# FOTA.net
KiCad netlist of a schematic drawn in Altium Designer
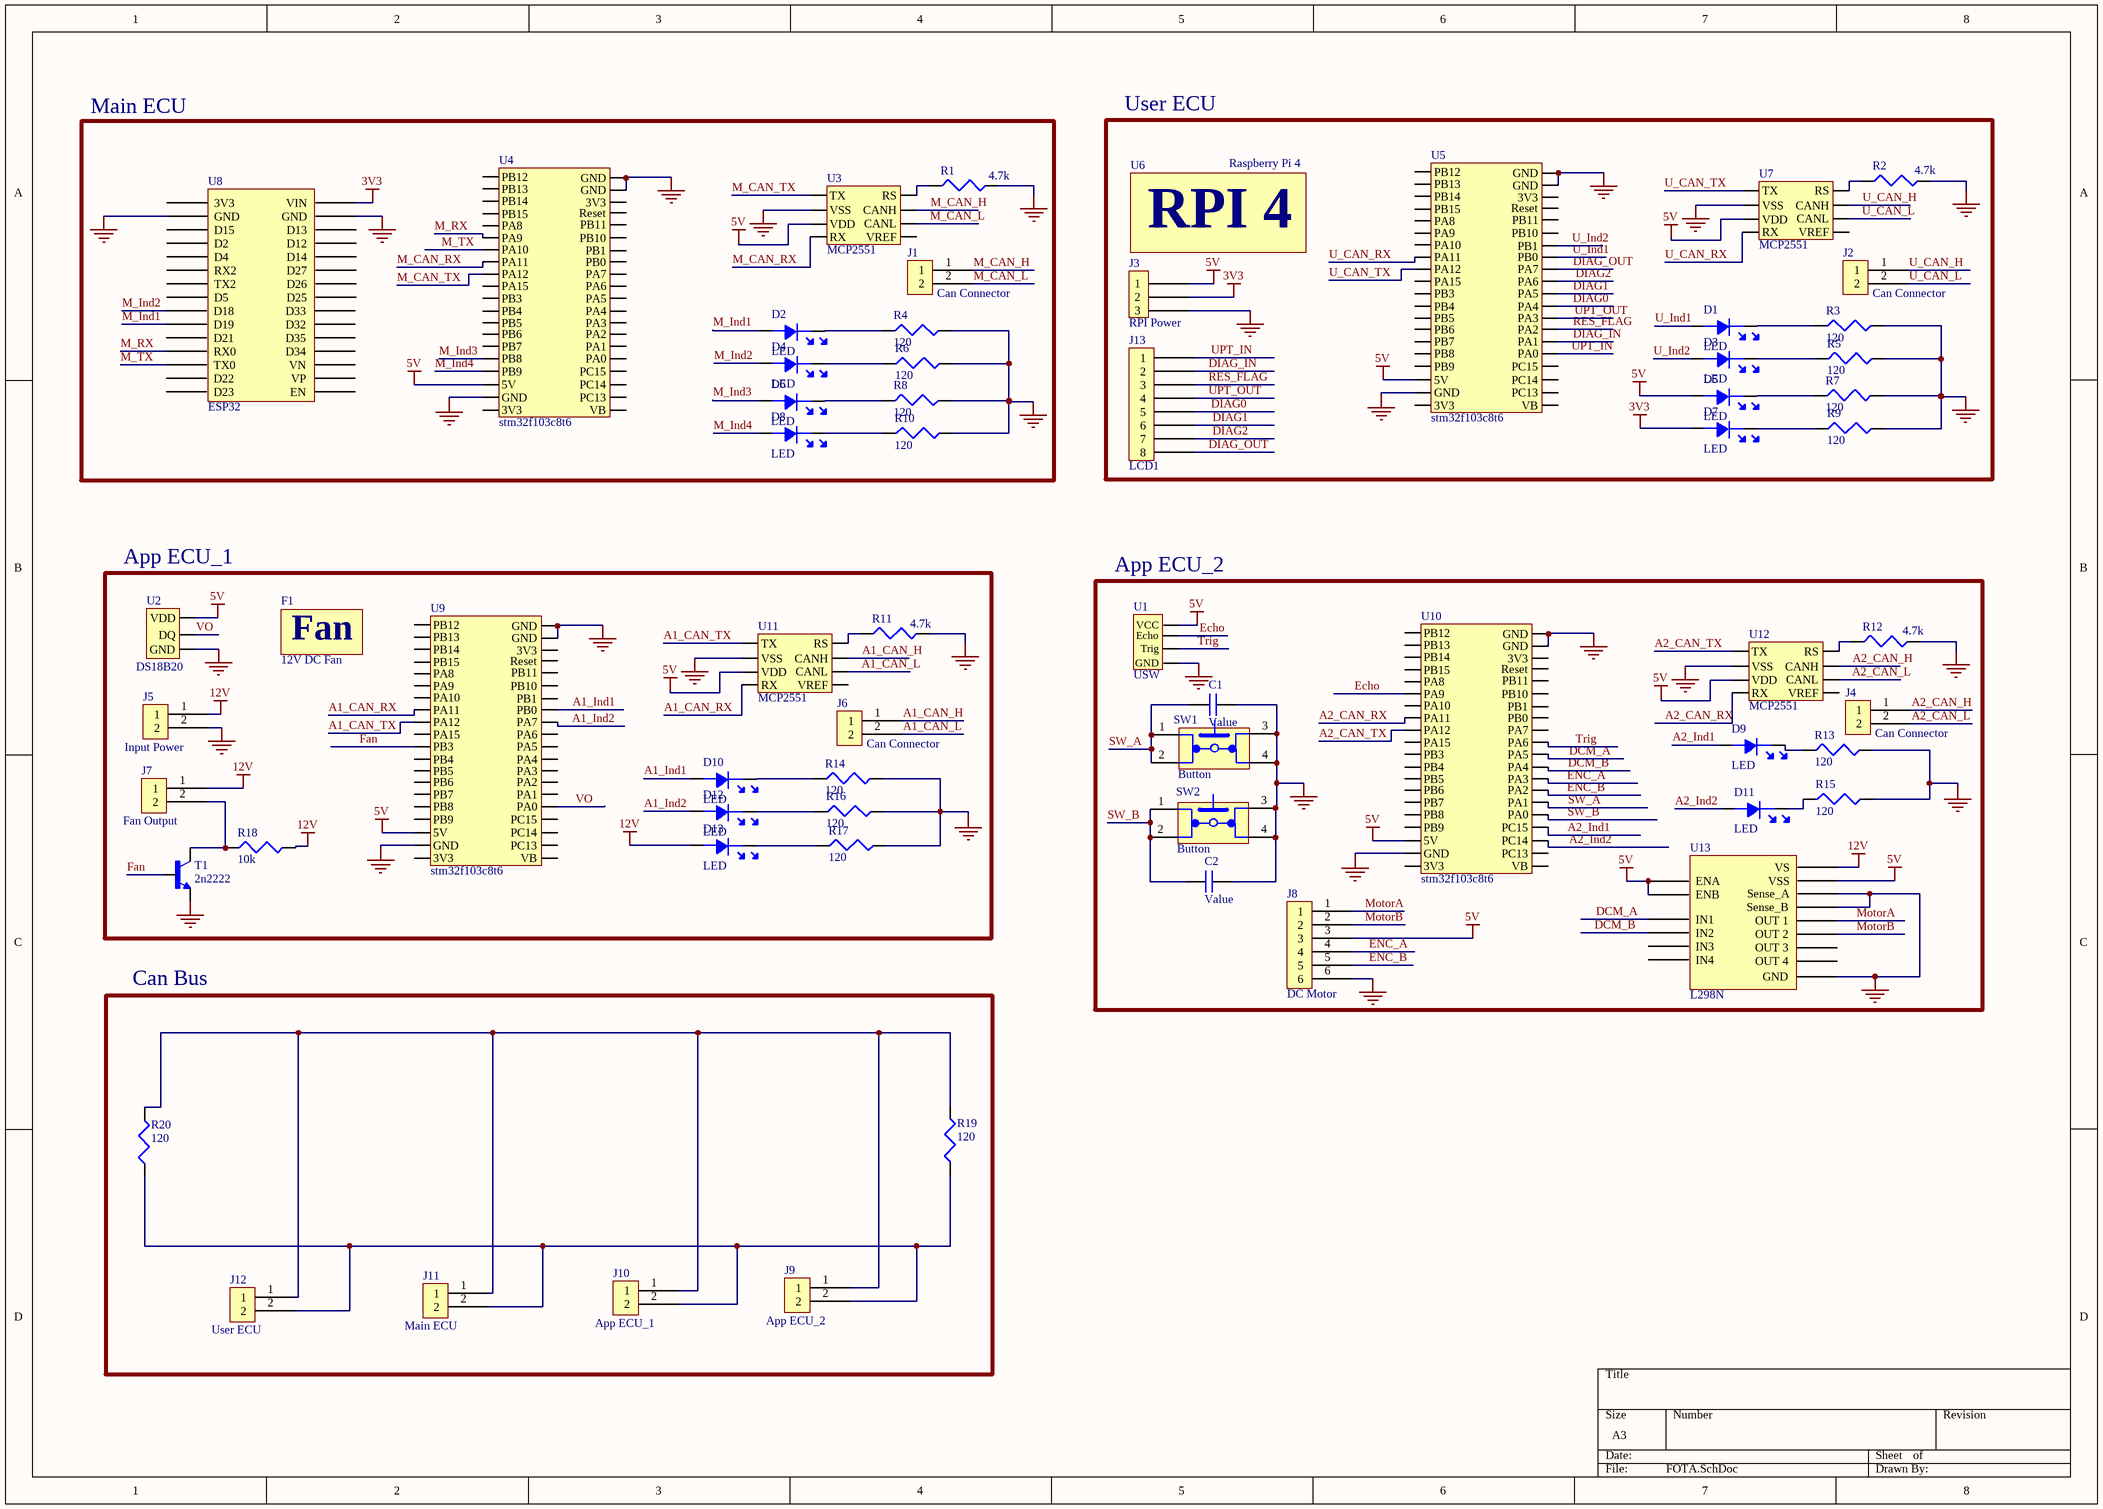
[diagram p0: FOTA.SchDoc]

(export (version "E")
  (design (tool "Eeschema 10.0.6"))
  (components
    (comp (ref "C1")
      (value "Value")
      (footprint "CAP non")
      (description "Generial Non polarized capacitor for through hole or SMD capacitors")
      (libsource (lib "FOTA") (part "Non polarized capacitor"))
    )
    (comp (ref "C2")
      (value "Value")
      (footprint "CAP non")
      (description "Generial Non polarized capacitor for through hole or SMD capacitors")
      (libsource (lib "FOTA") (part "Non polarized capacitor"))
    )
    (comp (ref "D1")
      (value "LED")
      (footprint "LED")
      (description "Led, Red, T-1 (3Mm), 630 Nm, 1.8 V, 30 Ma, 20 Mcd Rohs Compliant: Yes")
      (libsource (lib "FOTA") (part "LED"))
    )
    (comp (ref "D2")
      (value "LED")
      (footprint "LED")
      (description "Led, Red, T-1 (3Mm), 630 Nm, 1.8 V, 30 Ma, 20 Mcd Rohs Compliant: Yes")
      (libsource (lib "FOTA") (part "LED"))
    )
    (comp (ref "D3")
      (value "LED")
      (footprint "LED")
      (description "Led, Red, T-1 (3Mm), 630 Nm, 1.8 V, 30 Ma, 20 Mcd Rohs Compliant: Yes")
      (libsource (lib "FOTA") (part "LED"))
    )
    (comp (ref "D4")
      (value "LED")
      (footprint "LED")
      (description "Led, Red, T-1 (3Mm), 630 Nm, 1.8 V, 30 Ma, 20 Mcd Rohs Compliant: Yes")
      (libsource (lib "FOTA") (part "LED"))
    )
    (comp (ref "D5")
      (value "LED")
      (footprint "LED")
      (description "Led, Red, T-1 (3Mm), 630 Nm, 1.8 V, 30 Ma, 20 Mcd Rohs Compliant: Yes")
      (libsource (lib "FOTA") (part "LED"))
    )
    (comp (ref "D6")
      (value "LED")
      (footprint "LED")
      (description "Led, Red, T-1 (3Mm), 630 Nm, 1.8 V, 30 Ma, 20 Mcd Rohs Compliant: Yes")
      (libsource (lib "FOTA") (part "LED"))
    )
    (comp (ref "D7")
      (value "LED")
      (footprint "LED")
      (description "Led, Red, T-1 (3Mm), 630 Nm, 1.8 V, 30 Ma, 20 Mcd Rohs Compliant: Yes")
      (libsource (lib "FOTA") (part "LED"))
    )
    (comp (ref "D8")
      (value "LED")
      (footprint "LED")
      (description "Led, Red, T-1 (3Mm), 630 Nm, 1.8 V, 30 Ma, 20 Mcd Rohs Compliant: Yes")
      (libsource (lib "FOTA") (part "LED"))
    )
    (comp (ref "D9")
      (value "LED")
      (footprint "LED")
      (description "Led, Red, T-1 (3Mm), 630 Nm, 1.8 V, 30 Ma, 20 Mcd Rohs Compliant: Yes")
      (libsource (lib "FOTA") (part "LED"))
    )
    (comp (ref "D10")
      (value "LED")
      (footprint "LED")
      (description "Led, Red, T-1 (3Mm), 630 Nm, 1.8 V, 30 Ma, 20 Mcd Rohs Compliant: Yes")
      (libsource (lib "FOTA") (part "LED"))
    )
    (comp (ref "D11")
      (value "LED")
      (footprint "LED")
      (description "Led, Red, T-1 (3Mm), 630 Nm, 1.8 V, 30 Ma, 20 Mcd Rohs Compliant: Yes")
      (libsource (lib "FOTA") (part "LED"))
    )
    (comp (ref "D12")
      (value "LED")
      (footprint "LED")
      (description "Led, Red, T-1 (3Mm), 630 Nm, 1.8 V, 30 Ma, 20 Mcd Rohs Compliant: Yes")
      (libsource (lib "FOTA") (part "LED"))
    )
    (comp (ref "D13")
      (value "LED")
      (footprint "LED")
      (description "Led, Red, T-1 (3Mm), 630 Nm, 1.8 V, 30 Ma, 20 Mcd Rohs Compliant: Yes")
      (libsource (lib "FOTA") (part "LED"))
    )
    (comp (ref "F1") (value "12V DC Fan") (libsource (lib "FOTA") (part "Fan")))
    (comp (ref "J1")
      (value "Can Connector")
      (footprint "Data Connnector 2 pins")
      (libsource (lib "FOTA") (part "Data Connector 2 pins"))
    )
    (comp (ref "J2")
      (value "Can Connector")
      (footprint "Data Connnector 2 pins")
      (libsource (lib "FOTA") (part "Data Connector 2 pins"))
    )
    (comp (ref "J3")
      (value "RPI Power")
      (footprint "Data Connnector 3 pins")
      (libsource (lib "FOTA") (part "Data Connector 3 pin"))
    )
    (comp (ref "J4")
      (value "Can Connector")
      (footprint "Data Connnector 2 pins")
      (libsource (lib "FOTA") (part "Data Connector 2 pins"))
    )
    (comp (ref "J5")
      (value "Input Power")
      (footprint "Data Connnector 2 pins")
      (libsource (lib "FOTA") (part "Data Connector 2 pins"))
    )
    (comp (ref "J6")
      (value "Can Connector")
      (footprint "Data Connnector 2 pins")
      (libsource (lib "FOTA") (part "Data Connector 2 pins"))
    )
    (comp (ref "J7")
      (value "Fan Output")
      (footprint "Data Connnector 2 pins")
      (libsource (lib "FOTA") (part "Data Connector 2 pins"))
    )
    (comp (ref "J8")
      (value "DC Motor")
      (footprint "Data Connnector 6 pins")
      (libsource (lib "FOTA") (part "Data Connector 6 pin"))
    )
    (comp (ref "J9")
      (value "App ECU_2")
      (footprint "Data Connnector 2 pins")
      (libsource (lib "FOTA") (part "Data Connector 2 pins"))
    )
    (comp (ref "J10")
      (value "App ECU_1")
      (footprint "Data Connnector 2 pins")
      (libsource (lib "FOTA") (part "Data Connector 2 pins"))
    )
    (comp (ref "J11")
      (value "Main ECU")
      (footprint "Data Connnector 2 pins")
      (libsource (lib "FOTA") (part "Data Connector 2 pins"))
    )
    (comp (ref "J12")
      (value "User ECU")
      (footprint "Data Connnector 2 pins")
      (libsource (lib "FOTA") (part "Data Connector 2 pins"))
    )
    (comp (ref "J13")
      (value "LCD1")
      (footprint "Data Connector 8 pins")
      (libsource (lib "FOTA") (part "Data Connector 8 pins"))
    )
    (comp (ref "R1")
      (value "4.7k")
      (footprint "4.7k")
      (description "Res Carbon Film 4.7K Ohm 5% 1/4W -500ppm/°C to 350ppm/°C Conformal AXL Thru-Hole Paper T/R")
      (fields (field (name "TOLERANCE") "5%"))
      (libsource (lib "FOTA") (part "R 4K7"))
    )
    (comp (ref "R2")
      (value "4.7k")
      (footprint "4.7k")
      (description "Res Carbon Film 4.7K Ohm 5% 1/4W -500ppm/°C to 350ppm/°C Conformal AXL Thru-Hole Paper T/R")
      (fields (field (name "TOLERANCE") "5%"))
      (libsource (lib "FOTA") (part "R 4K7"))
    )
    (comp (ref "R3")
      (value "120")
      (footprint "R120")
      (description "General Type Carbon Film Resistor 120Ohm 1/4W 5% Axial Bulk")
      (fields (field (name "TOLERANCE") "5%"))
      (libsource (lib "FOTA") (part "R120"))
    )
    (comp (ref "R4")
      (value "120")
      (footprint "R120")
      (description "General Type Carbon Film Resistor 120Ohm 1/4W 5% Axial Bulk")
      (fields (field (name "TOLERANCE") "5%"))
      (libsource (lib "FOTA") (part "R120"))
    )
    (comp (ref "R5")
      (value "120")
      (footprint "R120")
      (description "General Type Carbon Film Resistor 120Ohm 1/4W 5% Axial Bulk")
      (fields (field (name "TOLERANCE") "5%"))
      (libsource (lib "FOTA") (part "R120"))
    )
    (comp (ref "R6")
      (value "120")
      (footprint "R120")
      (description "General Type Carbon Film Resistor 120Ohm 1/4W 5% Axial Bulk")
      (fields (field (name "TOLERANCE") "5%"))
      (libsource (lib "FOTA") (part "R120"))
    )
    (comp (ref "R7")
      (value "120")
      (footprint "R120")
      (description "General Type Carbon Film Resistor 120Ohm 1/4W 5% Axial Bulk")
      (fields (field (name "TOLERANCE") "5%"))
      (libsource (lib "FOTA") (part "R120"))
    )
    (comp (ref "R8")
      (value "120")
      (footprint "R120")
      (description "General Type Carbon Film Resistor 120Ohm 1/4W 5% Axial Bulk")
      (fields (field (name "TOLERANCE") "5%"))
      (libsource (lib "FOTA") (part "R120"))
    )
    (comp (ref "R9")
      (value "120")
      (footprint "R120")
      (description "General Type Carbon Film Resistor 120Ohm 1/4W 5% Axial Bulk")
      (fields (field (name "TOLERANCE") "5%"))
      (libsource (lib "FOTA") (part "R120"))
    )
    (comp (ref "R10")
      (value "120")
      (footprint "R120")
      (description "General Type Carbon Film Resistor 120Ohm 1/4W 5% Axial Bulk")
      (fields (field (name "TOLERANCE") "5%"))
      (libsource (lib "FOTA") (part "R120"))
    )
    (comp (ref "R11")
      (value "4.7k")
      (footprint "4.7k")
      (description "Res Carbon Film 4.7K Ohm 5% 1/4W -500ppm/°C to 350ppm/°C Conformal AXL Thru-Hole Paper T/R")
      (fields (field (name "TOLERANCE") "5%"))
      (libsource (lib "FOTA") (part "R 4K7"))
    )
    (comp (ref "R12")
      (value "4.7k")
      (footprint "4.7k")
      (description "Res Carbon Film 4.7K Ohm 5% 1/4W -500ppm/°C to 350ppm/°C Conformal AXL Thru-Hole Paper T/R")
      (fields (field (name "TOLERANCE") "5%"))
      (libsource (lib "FOTA") (part "R 4K7"))
    )
    (comp (ref "R13")
      (value "120")
      (footprint "R120")
      (description "General Type Carbon Film Resistor 120Ohm 1/4W 5% Axial Bulk")
      (fields (field (name "TOLERANCE") "5%"))
      (libsource (lib "FOTA") (part "R120"))
    )
    (comp (ref "R14")
      (value "120")
      (footprint "R120")
      (description "General Type Carbon Film Resistor 120Ohm 1/4W 5% Axial Bulk")
      (fields (field (name "TOLERANCE") "5%"))
      (libsource (lib "FOTA") (part "R120"))
    )
    (comp (ref "R15")
      (value "120")
      (footprint "R120")
      (description "General Type Carbon Film Resistor 120Ohm 1/4W 5% Axial Bulk")
      (fields (field (name "TOLERANCE") "5%"))
      (libsource (lib "FOTA") (part "R120"))
    )
    (comp (ref "R16")
      (value "120")
      (footprint "R120")
      (description "General Type Carbon Film Resistor 120Ohm 1/4W 5% Axial Bulk")
      (fields (field (name "TOLERANCE") "5%"))
      (libsource (lib "FOTA") (part "R120"))
    )
    (comp (ref "R17")
      (value "120")
      (footprint "R120")
      (description "General Type Carbon Film Resistor 120Ohm 1/4W 5% Axial Bulk")
      (fields (field (name "TOLERANCE") "5%"))
      (libsource (lib "FOTA") (part "R120"))
    )
    (comp (ref "R18")
      (value "10k")
      (footprint "10k")
      (description "Through Hole Carbon Film Resistor, Cfr Series, 10 Kohm, 250 Mw, - 5%, 200 V, Axial Leaded")
      (libsource (lib "FOTA") (part "R 10K"))
    )
    (comp (ref "R19") (value "120") (footprint "R120") (libsource (lib "FOTA") (part "R120_TH")))
    (comp (ref "R20") (value "120") (footprint "R120") (libsource (lib "FOTA") (part "R120_TH")))
    (comp (ref "SW1") (value "Button") (footprint "DIP4 SW") (libsource (lib "FOTA") (part "Push Button")))
    (comp (ref "SW2") (value "Button") (footprint "DIP4 SW") (libsource (lib "FOTA") (part "Push Button")))
    (comp (ref "T1") (value "2n2222") (footprint "TRANS") (libsource (lib "FOTA") (part "2n2222")))
    (comp (ref "U1")
      (value "USW")
      (footprint "hc-sr04")
      (description "Ultrasonic Sensor Module, Rectangular, 20-4000 mm, 5 V, 15 mA, Arduino Compatible")
      (libsource (lib "FOTA") (part "HC-SR04"))
    )
    (comp (ref "U2")
      (value "DS18B20")
      (footprint "tmp")
      (description "SENSOR TEMPERATURE 1-WIRE TO92-3")
      (libsource (lib "FOTA") (part "DS18B20"))
    )
    (comp (ref "U3")
      (value "MCP2551")
      (footprint "MCP2551")
      (description "MCP2551 Series 5.5 V 1 Mb/s Surface Mount High-Speed CAN Transceiver - PDIP-8")
      (libsource (lib "FOTA") (part "MCP2551-I/P"))
    )
    (comp (ref "U4")
      (value "stm32f103c8t6")
      (footprint "DIP46")
      (description "STM32 Nucleo-32 development board with STM32F031K6 MCU, supports Arduino connectivity")
      (libsource (lib "FOTA") (part "stm32f103c8t6"))
    )
    (comp (ref "U5")
      (value "stm32f103c8t6")
      (footprint "DIP46")
      (description "STM32 Nucleo-32 development board with STM32F031K6 MCU, supports Arduino connectivity")
      (libsource (lib "FOTA") (part "stm32f103c8t6"))
    )
    (comp (ref "U6")
      (value "Raspberry Pi 4")
      (footprint "RPI4")
      (libsource (lib "FOTA") (part "Raspberry Pi 4"))
    )
    (comp (ref "U7")
      (value "MCP2551")
      (footprint "MCP2551")
      (description "MCP2551 Series 5.5 V 1 Mb/s Surface Mount High-Speed CAN Transceiver - PDIP-8")
      (libsource (lib "FOTA") (part "MCP2551-I/P"))
    )
    (comp (ref "U8") (value "ESP32") (footprint "ESP32") (libsource (lib "FOTA") (part "ESP32")))
    (comp (ref "U9")
      (value "stm32f103c8t6")
      (footprint "DIP46")
      (description "STM32 Nucleo-32 development board with STM32F031K6 MCU, supports Arduino connectivity")
      (libsource (lib "FOTA") (part "stm32f103c8t6"))
    )
    (comp (ref "U10")
      (value "stm32f103c8t6")
      (footprint "DIP46")
      (description "STM32 Nucleo-32 development board with STM32F031K6 MCU, supports Arduino connectivity")
      (libsource (lib "FOTA") (part "stm32f103c8t6"))
    )
    (comp (ref "U11")
      (value "MCP2551")
      (footprint "MCP2551")
      (description "MCP2551 Series 5.5 V 1 Mb/s Surface Mount High-Speed CAN Transceiver - PDIP-8")
      (libsource (lib "FOTA") (part "MCP2551-I/P"))
    )
    (comp (ref "U12")
      (value "MCP2551")
      (footprint "MCP2551")
      (description "MCP2551 Series 5.5 V 1 Mb/s Surface Mount High-Speed CAN Transceiver - PDIP-8")
      (libsource (lib "FOTA") (part "MCP2551-I/P"))
    )
    (comp (ref "U13") (value "L298N") (footprint "L298") (libsource (lib "FOTA") (part "L298N Breakout")))
  )
  (nets
    (net (code "1") (name "/A1_CAN_H") (class "Default")
      (node (ref "J6") (pin "1") (pinfunction "1_1") (pintype "passive"))
      (node (ref "U11") (pin "7") (pinfunction "CANH_7") (pintype "passive"))
    )
    (net (code "2") (name "/A1_CAN_L") (class "Default")
      (node (ref "J6") (pin "2") (pinfunction "2_2") (pintype "passive"))
      (node (ref "U11") (pin "6") (pinfunction "CANL_6") (pintype "passive"))
    )
    (net (code "3") (name "/A1_CAN_RX") (class "Default")
      (node (ref "U11") (pin "4") (pinfunction "RX_4") (pintype "passive"))
      (node (ref "U9") (pin "34") (pinfunction "PA11_34") (pintype "passive"))
    )
    (net (code "4") (name "/A1_CAN_TX") (class "Default")
      (node (ref "U11") (pin "1") (pinfunction "TX_1") (pintype "passive"))
      (node (ref "U9") (pin "35") (pinfunction "PA12_35") (pintype "passive"))
    )
    (net (code "5") (name "/A1_Ind1") (class "Default")
      (node (ref "D10") (pin "1") (pinfunction "1_1") (pintype "passive"))
      (node (ref "U9") (pin "13") (pinfunction "PB0_13") (pintype "passive"))
    )
    (net (code "6") (name "/A1_Ind2") (class "Default")
      (node (ref "D12") (pin "1") (pinfunction "1_1") (pintype "passive"))
      (node (ref "U9") (pin "12") (pinfunction "PA7_12") (pintype "passive"))
    )
    (net (code "7") (name "/A2_CAN_H") (class "Default")
      (node (ref "J4") (pin "1") (pinfunction "1_1") (pintype "passive"))
      (node (ref "U12") (pin "7") (pinfunction "CANH_7") (pintype "passive"))
    )
    (net (code "8") (name "/A2_CAN_L") (class "Default")
      (node (ref "J4") (pin "2") (pinfunction "2_2") (pintype "passive"))
      (node (ref "U12") (pin "6") (pinfunction "CANL_6") (pintype "passive"))
    )
    (net (code "9") (name "/A2_CAN_RX") (class "Default")
      (node (ref "U10") (pin "34") (pinfunction "PA11_34") (pintype "passive"))
      (node (ref "U12") (pin "4") (pinfunction "RX_4") (pintype "passive"))
    )
    (net (code "10") (name "/A2_CAN_TX") (class "Default")
      (node (ref "U10") (pin "35") (pinfunction "PA12_35") (pintype "passive"))
      (node (ref "U12") (pin "1") (pinfunction "TX_1") (pintype "passive"))
    )
    (net (code "11") (name "/A2_Ind1") (class "Default")
      (node (ref "D9") (pin "1") (pinfunction "1_1") (pintype "passive"))
      (node (ref "U10") (pin "4") (pinfunction "PC15_4") (pintype "passive"))
    )
    (net (code "12") (name "/A2_Ind2") (class "Default")
      (node (ref "D11") (pin "1") (pinfunction "1_1") (pintype "passive"))
      (node (ref "U10") (pin "3") (pinfunction "PC14_3") (pintype "passive"))
    )
    (net (code "13") (name "/DCM_A") (class "Default")
      (node (ref "U10") (pin "10") (pinfunction "PA5_10") (pintype "passive"))
      (node (ref "U13") (pin "8") (pinfunction "IN1_8") (pintype "passive"))
    )
    (net (code "14") (name "/DCM_B") (class "Default")
      (node (ref "U10") (pin "9") (pinfunction "PA4_9") (pintype "passive"))
      (node (ref "U13") (pin "7") (pinfunction "IN2_7") (pintype "passive"))
    )
    (net (code "15") (name "/DIAG0") (class "Default")
      (node (ref "J13") (pin "5") (pinfunction "5_5") (pintype "passive"))
      (node (ref "U5") (pin "9") (pinfunction "PA4_9") (pintype "passive"))
    )
    (net (code "16") (name "/DIAG1") (class "Default")
      (node (ref "J13") (pin "6") (pinfunction "6_6") (pintype "passive"))
      (node (ref "U5") (pin "10") (pinfunction "PA5_10") (pintype "passive"))
    )
    (net (code "17") (name "/DIAG2") (class "Default")
      (node (ref "J13") (pin "7") (pinfunction "7_7") (pintype "passive"))
      (node (ref "U5") (pin "11") (pinfunction "PA6_11") (pintype "passive"))
    )
    (net (code "18") (name "/DIAG_IN") (class "Default")
      (node (ref "J13") (pin "2") (pinfunction "2_2") (pintype "passive"))
      (node (ref "U5") (pin "6") (pinfunction "PA1_6") (pintype "passive"))
    )
    (net (code "19") (name "/DIAG_OUT") (class "Default")
      (node (ref "J13") (pin "8") (pinfunction "8_8") (pintype "passive"))
      (node (ref "U5") (pin "12") (pinfunction "PA7_12") (pintype "passive"))
    )
    (net (code "20") (name "/ENC_A") (class "Default")
      (node (ref "J8") (pin "4") (pinfunction "4_4") (pintype "passive"))
      (node (ref "U10") (pin "8") (pinfunction "PA3_8") (pintype "passive"))
    )
    (net (code "21") (name "/ENC_B") (class "Default")
      (node (ref "J8") (pin "5") (pinfunction "5_5") (pintype "passive"))
      (node (ref "U10") (pin "7") (pinfunction "PA2_7") (pintype "passive"))
    )
    (net (code "22") (name "/Echo") (class "Default")
      (node (ref "U1") (pin "3") (pinfunction "Echo_3") (pintype "passive"))
      (node (ref "U10") (pin "32") (pinfunction "PA9_32") (pintype "passive"))
    )
    (net (code "23") (name "/Fan") (class "Default")
      (node (ref "T1") (pin "2") (pinfunction "B_2") (pintype "passive"))
      (node (ref "U9") (pin "37") (pinfunction "PB3_37") (pintype "passive"))
    )
    (net (code "24") (name "/M_CAN_H") (class "Default")
      (node (ref "J1") (pin "1") (pinfunction "1_1") (pintype "passive"))
      (node (ref "U3") (pin "7") (pinfunction "CANH_7") (pintype "passive"))
    )
    (net (code "25") (name "/M_CAN_L") (class "Default")
      (node (ref "J1") (pin "2") (pinfunction "2_2") (pintype "passive"))
      (node (ref "U3") (pin "6") (pinfunction "CANL_6") (pintype "passive"))
    )
    (net (code "26") (name "/M_CAN_RX") (class "Default")
      (node (ref "U3") (pin "4") (pinfunction "RX_4") (pintype "passive"))
      (node (ref "U4") (pin "34") (pinfunction "PA11_34") (pintype "passive"))
    )
    (net (code "27") (name "/M_CAN_TX") (class "Default")
      (node (ref "U3") (pin "1") (pinfunction "TX_1") (pintype "passive"))
      (node (ref "U4") (pin "35") (pinfunction "PA12_35") (pintype "passive"))
    )
    (net (code "28") (name "/M_Ind1") (class "Default")
      (node (ref "D2") (pin "1") (pinfunction "1_1") (pintype "passive"))
      (node (ref "U8") (pin "10") (pinfunction "D19_10") (pintype "passive"))
    )
    (net (code "29") (name "/M_Ind2") (class "Default")
      (node (ref "D4") (pin "1") (pinfunction "1_1") (pintype "passive"))
      (node (ref "U8") (pin "9") (pinfunction "D18_9") (pintype "passive"))
    )
    (net (code "30") (name "/M_Ind3") (class "Default")
      (node (ref "D6") (pin "1") (pinfunction "1_1") (pintype "passive"))
      (node (ref "U4") (pin "42") (pinfunction "PB8_42") (pintype "passive"))
    )
    (net (code "31") (name "/M_Ind4") (class "Default")
      (node (ref "D8") (pin "1") (pinfunction "1_1") (pintype "passive"))
      (node (ref "U4") (pin "43") (pinfunction "PB9_43") (pintype "passive"))
    )
    (net (code "32") (name "/M_RX") (class "Default")
      (node (ref "U4") (pin "32") (pinfunction "PA9_32") (pintype "passive"))
      (node (ref "U8") (pin "12") (pinfunction "RX0_12") (pintype "passive"))
    )
    (net (code "33") (name "/M_TX") (class "Default")
      (node (ref "U4") (pin "33") (pinfunction "PA10_33") (pintype "passive"))
      (node (ref "U8") (pin "13") (pinfunction "TX0_13") (pintype "passive"))
    )
    (net (code "34") (name "/MotorA") (class "Default")
      (node (ref "J8") (pin "1") (pinfunction "1_1") (pintype "passive"))
      (node (ref "U13") (pin "4") (pinfunction "OUT_1_4") (pintype "passive"))
    )
    (net (code "35") (name "/MotorB") (class "Default")
      (node (ref "J8") (pin "2") (pinfunction "2_2") (pintype "passive"))
      (node (ref "U13") (pin "3") (pinfunction "OUT_2_3") (pintype "passive"))
    )
    (net (code "36") (name "/RES_FLAG") (class "Default")
      (node (ref "J13") (pin "3") (pinfunction "3_3") (pintype "passive"))
      (node (ref "U5") (pin "7") (pinfunction "PA2_7") (pintype "passive"))
    )
    (net (code "37") (name "/SW_A") (class "Default")
      (node (ref "C1") (pin "1") (pinfunction "1_1") (pintype "passive"))
      (node (ref "SW1") (pin "1") (pinfunction "1_1") (pintype "passive"))
      (node (ref "SW1") (pin "2") (pinfunction "2_2") (pintype "passive"))
      (node (ref "U10") (pin "6") (pinfunction "PA1_6") (pintype "passive"))
    )
    (net (code "38") (name "/SW_B") (class "Default")
      (node (ref "C2") (pin "1") (pinfunction "1_1") (pintype "passive"))
      (node (ref "SW2") (pin "1") (pinfunction "1_1") (pintype "passive"))
      (node (ref "SW2") (pin "2") (pinfunction "2_2") (pintype "passive"))
      (node (ref "U10") (pin "5") (pinfunction "PA0_5") (pintype "passive"))
    )
    (net (code "39") (name "/Trig") (class "Default")
      (node (ref "U1") (pin "2") (pinfunction "Trig_2") (pintype "passive"))
      (node (ref "U10") (pin "11") (pinfunction "PA6_11") (pintype "passive"))
    )
    (net (code "40") (name "/UPT_IN") (class "Default")
      (node (ref "J13") (pin "1") (pinfunction "1_1") (pintype "passive"))
      (node (ref "U5") (pin "5") (pinfunction "PA0_5") (pintype "passive"))
    )
    (net (code "41") (name "/UPT_OUT") (class "Default")
      (node (ref "J13") (pin "4") (pinfunction "4_4") (pintype "passive"))
      (node (ref "U5") (pin "8") (pinfunction "PA3_8") (pintype "passive"))
    )
    (net (code "42") (name "/U_CAN_H") (class "Default")
      (node (ref "J2") (pin "1") (pinfunction "1_1") (pintype "passive"))
      (node (ref "U7") (pin "7") (pinfunction "CANH_7") (pintype "passive"))
    )
    (net (code "43") (name "/U_CAN_L") (class "Default")
      (node (ref "J2") (pin "2") (pinfunction "2_2") (pintype "passive"))
      (node (ref "U7") (pin "6") (pinfunction "CANL_6") (pintype "passive"))
    )
    (net (code "44") (name "/U_CAN_RX") (class "Default")
      (node (ref "U5") (pin "34") (pinfunction "PA11_34") (pintype "passive"))
      (node (ref "U7") (pin "4") (pinfunction "RX_4") (pintype "passive"))
    )
    (net (code "45") (name "/U_CAN_TX") (class "Default")
      (node (ref "U5") (pin "35") (pinfunction "PA12_35") (pintype "passive"))
      (node (ref "U7") (pin "1") (pinfunction "TX_1") (pintype "passive"))
    )
    (net (code "46") (name "/U_Ind1") (class "Default")
      (node (ref "D1") (pin "1") (pinfunction "1_1") (pintype "passive"))
      (node (ref "U5") (pin "13") (pinfunction "PB0_13") (pintype "passive"))
    )
    (net (code "47") (name "/U_Ind2") (class "Default")
      (node (ref "D3") (pin "1") (pinfunction "1_1") (pintype "passive"))
      (node (ref "U5") (pin "14") (pinfunction "PB1_14") (pintype "passive"))
    )
    (net (code "48") (name "/VO") (class "Default")
      (node (ref "U2") (pin "2") (pinfunction "DQ_2") (pintype "passive"))
      (node (ref "U9") (pin "5") (pinfunction "PA0_5") (pintype "passive"))
    )
    (net (code "49") (name "3V3") (class "Default")
      (node (ref "D7") (pin "1") (pinfunction "1_1") (pintype "passive"))
      (node (ref "J3") (pin "2") (pinfunction "2_2") (pintype "passive"))
      (node (ref "U8") (pin "30") (pinfunction "VIN_30") (pintype "passive"))
    )
    (net (code "50") (name "5V") (class "Default")
      (node (ref "D5") (pin "1") (pinfunction "1_1") (pintype "passive"))
      (node (ref "J3") (pin "1") (pinfunction "1_1") (pintype "passive"))
      (node (ref "J8") (pin "3") (pinfunction "3_3") (pintype "passive"))
      (node (ref "U1") (pin "1") (pinfunction "VCC_1") (pintype "passive"))
      (node (ref "U10") (pin "44") (pinfunction "5V_44") (pintype "passive"))
      (node (ref "U11") (pin "3") (pinfunction "VDD_3") (pintype "passive"))
      (node (ref "U12") (pin "3") (pinfunction "VDD_3") (pintype "passive"))
      (node (ref "U13") (pin "10") (pinfunction "ENA_10") (pintype "passive"))
      (node (ref "U13") (pin "13") (pinfunction "VSS_13") (pintype "passive"))
      (node (ref "U13") (pin "9") (pinfunction "ENB_9") (pintype "passive"))
      (node (ref "U2") (pin "1") (pinfunction "VDD_1") (pintype "passive"))
      (node (ref "U3") (pin "3") (pinfunction "VDD_3") (pintype "passive"))
      (node (ref "U4") (pin "44") (pinfunction "5V_44") (pintype "passive"))
      (node (ref "U5") (pin "44") (pinfunction "5V_44") (pintype "passive"))
      (node (ref "U7") (pin "3") (pinfunction "VDD_3") (pintype "passive"))
      (node (ref "U9") (pin "44") (pinfunction "5V_44") (pintype "passive"))
    )
    (net (code "51") (name "12V") (class "Default")
      (node (ref "D13") (pin "1") (pinfunction "1_1") (pintype "passive"))
      (node (ref "J5") (pin "1") (pinfunction "1_1") (pintype "passive"))
      (node (ref "J7") (pin "1") (pinfunction "1_1") (pintype "passive"))
      (node (ref "R18") (pin "1") (pinfunction "1_1") (pintype "passive"))
      (node (ref "U13") (pin "14") (pinfunction "VS_14") (pintype "passive"))
    )
    (net (code "52") (name "GND") (class "Default")
      (node (ref "C1") (pin "2") (pinfunction "2_2") (pintype "passive"))
      (node (ref "C2") (pin "2") (pinfunction "2_2") (pintype "passive"))
      (node (ref "J3") (pin "3") (pinfunction "3_3") (pintype "passive"))
      (node (ref "J5") (pin "2") (pinfunction "2_2") (pintype "passive"))
      (node (ref "J8") (pin "6") (pinfunction "6_6") (pintype "passive"))
      (node (ref "R1") (pin "1") (pinfunction "1_1") (pintype "passive"))
      (node (ref "R10") (pin "1") (pinfunction "1_1") (pintype "passive"))
      (node (ref "R11") (pin "1") (pinfunction "1_1") (pintype "passive"))
      (node (ref "R12") (pin "1") (pinfunction "1_1") (pintype "passive"))
      (node (ref "R13") (pin "1") (pinfunction "1_1") (pintype "passive"))
      (node (ref "R14") (pin "1") (pinfunction "1_1") (pintype "passive"))
      (node (ref "R15") (pin "1") (pinfunction "1_1") (pintype "passive"))
      (node (ref "R16") (pin "1") (pinfunction "1_1") (pintype "passive"))
      (node (ref "R17") (pin "1") (pinfunction "1_1") (pintype "passive"))
      (node (ref "R2") (pin "1") (pinfunction "1_1") (pintype "passive"))
      (node (ref "R3") (pin "1") (pinfunction "1_1") (pintype "passive"))
      (node (ref "R4") (pin "1") (pinfunction "1_1") (pintype "passive"))
      (node (ref "R5") (pin "1") (pinfunction "1_1") (pintype "passive"))
      (node (ref "R6") (pin "1") (pinfunction "1_1") (pintype "passive"))
      (node (ref "R7") (pin "1") (pinfunction "1_1") (pintype "passive"))
      (node (ref "R8") (pin "1") (pinfunction "1_1") (pintype "passive"))
      (node (ref "R9") (pin "1") (pinfunction "1_1") (pintype "passive"))
      (node (ref "SW1") (pin "3") (pinfunction "3_3") (pintype "passive"))
      (node (ref "SW1") (pin "4") (pinfunction "4_4") (pintype "passive"))
      (node (ref "SW2") (pin "3") (pinfunction "3_3") (pintype "passive"))
      (node (ref "SW2") (pin "4") (pinfunction "4_4") (pintype "passive"))
      (node (ref "T1") (pin "1") (pinfunction "E_1") (pintype "passive"))
      (node (ref "U1") (pin "4") (pinfunction "GND_4") (pintype "passive"))
      (node (ref "U10") (pin "19") (pinfunction "GND_19") (pintype "passive"))
      (node (ref "U10") (pin "20") (pinfunction "GND_20") (pintype "passive"))
      (node (ref "U10") (pin "45") (pinfunction "GND_45") (pintype "passive"))
      (node (ref "U11") (pin "2") (pinfunction "VSS_2") (pintype "passive"))
      (node (ref "U12") (pin "2") (pinfunction "VSS_2") (pintype "passive"))
      (node (ref "U13") (pin "11") (pinfunction "Sense_B_11") (pintype "passive"))
      (node (ref "U13") (pin "12") (pinfunction "Sense_A_12") (pintype "passive"))
      (node (ref "U13") (pin "15") (pinfunction "GND_15") (pintype "passive"))
      (node (ref "U2") (pin "3") (pinfunction "GND_3") (pintype "passive"))
      (node (ref "U3") (pin "2") (pinfunction "VSS_2") (pintype "passive"))
      (node (ref "U4") (pin "19") (pinfunction "GND_19") (pintype "passive"))
      (node (ref "U4") (pin "20") (pinfunction "GND_20") (pintype "passive"))
      (node (ref "U4") (pin "45") (pinfunction "GND_45") (pintype "passive"))
      (node (ref "U5") (pin "19") (pinfunction "GND_19") (pintype "passive"))
      (node (ref "U5") (pin "20") (pinfunction "GND_20") (pintype "passive"))
      (node (ref "U5") (pin "45") (pinfunction "GND_45") (pintype "passive"))
      (node (ref "U7") (pin "2") (pinfunction "VSS_2") (pintype "passive"))
      (node (ref "U8") (pin "2") (pinfunction "GND_2") (pintype "passive"))
      (node (ref "U8") (pin "29") (pinfunction "GND_29") (pintype "passive"))
      (node (ref "U9") (pin "19") (pinfunction "GND_19") (pintype "passive"))
      (node (ref "U9") (pin "20") (pinfunction "GND_20") (pintype "passive"))
      (node (ref "U9") (pin "45") (pinfunction "GND_45") (pintype "passive"))
    )
    (net (code "53") (name "Net-(D1-Pad2)") (class "Default")
      (node (ref "D1") (pin "2") (pinfunction "2_2") (pintype "passive"))
      (node (ref "R3") (pin "2") (pinfunction "2_2") (pintype "passive"))
    )
    (net (code "54") (name "Net-(D2-Pad2)") (class "Default")
      (node (ref "D2") (pin "2") (pinfunction "2_2") (pintype "passive"))
      (node (ref "R4") (pin "2") (pinfunction "2_2") (pintype "passive"))
    )
    (net (code "55") (name "Net-(D3-Pad2)") (class "Default")
      (node (ref "D3") (pin "2") (pinfunction "2_2") (pintype "passive"))
      (node (ref "R5") (pin "2") (pinfunction "2_2") (pintype "passive"))
    )
    (net (code "56") (name "Net-(D4-Pad2)") (class "Default")
      (node (ref "D4") (pin "2") (pinfunction "2_2") (pintype "passive"))
      (node (ref "R6") (pin "2") (pinfunction "2_2") (pintype "passive"))
    )
    (net (code "57") (name "Net-(D5-Pad2)") (class "Default")
      (node (ref "D5") (pin "2") (pinfunction "2_2") (pintype "passive"))
      (node (ref "R7") (pin "2") (pinfunction "2_2") (pintype "passive"))
    )
    (net (code "58") (name "Net-(D6-Pad2)") (class "Default")
      (node (ref "D6") (pin "2") (pinfunction "2_2") (pintype "passive"))
      (node (ref "R8") (pin "2") (pinfunction "2_2") (pintype "passive"))
    )
    (net (code "59") (name "Net-(D7-Pad2)") (class "Default")
      (node (ref "D7") (pin "2") (pinfunction "2_2") (pintype "passive"))
      (node (ref "R9") (pin "2") (pinfunction "2_2") (pintype "passive"))
    )
    (net (code "60") (name "Net-(D8-Pad2)") (class "Default")
      (node (ref "D8") (pin "2") (pinfunction "2_2") (pintype "passive"))
      (node (ref "R10") (pin "2") (pinfunction "2_2") (pintype "passive"))
    )
    (net (code "61") (name "Net-(D9-Pad2)") (class "Default")
      (node (ref "D9") (pin "2") (pinfunction "2_2") (pintype "passive"))
      (node (ref "R13") (pin "2") (pinfunction "2_2") (pintype "passive"))
    )
    (net (code "62") (name "Net-(D10-Pad2)") (class "Default")
      (node (ref "D10") (pin "2") (pinfunction "2_2") (pintype "passive"))
      (node (ref "R14") (pin "2") (pinfunction "2_2") (pintype "passive"))
    )
    (net (code "63") (name "Net-(D11-Pad2)") (class "Default")
      (node (ref "D11") (pin "2") (pinfunction "2_2") (pintype "passive"))
      (node (ref "R15") (pin "2") (pinfunction "2_2") (pintype "passive"))
    )
    (net (code "64") (name "Net-(D12-Pad2)") (class "Default")
      (node (ref "D12") (pin "2") (pinfunction "2_2") (pintype "passive"))
      (node (ref "R16") (pin "2") (pinfunction "2_2") (pintype "passive"))
    )
    (net (code "65") (name "Net-(D13-Pad2)") (class "Default")
      (node (ref "D13") (pin "2") (pinfunction "2_2") (pintype "passive"))
      (node (ref "R17") (pin "2") (pinfunction "2_2") (pintype "passive"))
    )
    (net (code "66") (name "Net-(J10-Pad1)") (class "Default")
      (node (ref "J10") (pin "1") (pinfunction "1_1") (pintype "passive"))
      (node (ref "J11") (pin "1") (pinfunction "1_1") (pintype "passive"))
      (node (ref "J12") (pin "1") (pinfunction "1_1") (pintype "passive"))
      (node (ref "J9") (pin "1") (pinfunction "1_1") (pintype "passive"))
      (node (ref "R19") (pin "1") (pinfunction "1_1") (pintype "passive"))
      (node (ref "R20") (pin "1") (pinfunction "1_1") (pintype "passive"))
    )
    (net (code "67") (name "Net-(J10-Pad2)") (class "Default")
      (node (ref "J10") (pin "2") (pinfunction "2_2") (pintype "passive"))
      (node (ref "J11") (pin "2") (pinfunction "2_2") (pintype "passive"))
      (node (ref "J12") (pin "2") (pinfunction "2_2") (pintype "passive"))
      (node (ref "J9") (pin "2") (pinfunction "2_2") (pintype "passive"))
      (node (ref "R19") (pin "2") (pinfunction "2_2") (pintype "passive"))
      (node (ref "R20") (pin "2") (pinfunction "2_2") (pintype "passive"))
    )
    (net (code "68") (name "Net-(T1-C)") (class "Default")
      (node (ref "J7") (pin "2") (pinfunction "2_2") (pintype "passive"))
      (node (ref "R18") (pin "2") (pinfunction "2_2") (pintype "passive"))
      (node (ref "T1") (pin "3") (pinfunction "C_3") (pintype "passive"))
    )
    (net (code "69") (name "Net-(U3-RS)") (class "Default")
      (node (ref "R1") (pin "2") (pinfunction "2_2") (pintype "passive"))
      (node (ref "U3") (pin "8") (pinfunction "RS_8") (pintype "passive"))
    )
    (net (code "70") (name "Net-(U7-RS)") (class "Default")
      (node (ref "R2") (pin "2") (pinfunction "2_2") (pintype "passive"))
      (node (ref "U7") (pin "8") (pinfunction "RS_8") (pintype "passive"))
    )
    (net (code "71") (name "Net-(U11-RS)") (class "Default")
      (node (ref "R11") (pin "2") (pinfunction "2_2") (pintype "passive"))
      (node (ref "U11") (pin "8") (pinfunction "RS_8") (pintype "passive"))
    )
    (net (code "72") (name "Net-(U12-RS)") (class "Default")
      (node (ref "R12") (pin "2") (pinfunction "2_2") (pintype "passive"))
      (node (ref "U12") (pin "8") (pinfunction "RS_8") (pintype "passive"))
    )
    (net (code "73") (name "unconnected-(U3-VREF-Pad5)") (class "Default")
      (node (ref "U3") (pin "5") (pinfunction "VREF_5") (pintype "passive"))
    )
    (net (code "74") (name "unconnected-(U4-3V3-Pad18)") (class "Default")
      (node (ref "U4") (pin "18") (pinfunction "3V3_18") (pintype "passive"))
    )
    (net (code "75") (name "unconnected-(U4-3V3-Pad46)") (class "Default")
      (node (ref "U4") (pin "46") (pinfunction "3V3_46") (pintype "passive"))
    )
    (net (code "76") (name "unconnected-(U4-PA0-Pad5)") (class "Default")
      (node (ref "U4") (pin "5") (pinfunction "PA0_5") (pintype "passive"))
    )
    (net (code "77") (name "unconnected-(U4-PA1-Pad6)") (class "Default")
      (node (ref "U4") (pin "6") (pinfunction "PA1_6") (pintype "passive"))
    )
    (net (code "78") (name "unconnected-(U4-PA2-Pad7)") (class "Default")
      (node (ref "U4") (pin "7") (pinfunction "PA2_7") (pintype "passive"))
    )
    (net (code "79") (name "unconnected-(U4-PA3-Pad8)") (class "Default")
      (node (ref "U4") (pin "8") (pinfunction "PA3_8") (pintype "passive"))
    )
    (net (code "80") (name "unconnected-(U4-PA4-Pad9)") (class "Default")
      (node (ref "U4") (pin "9") (pinfunction "PA4_9") (pintype "passive"))
    )
    (net (code "81") (name "unconnected-(U4-PA5-Pad10)") (class "Default")
      (node (ref "U4") (pin "10") (pinfunction "PA5_10") (pintype "passive"))
    )
    (net (code "82") (name "unconnected-(U4-PA6-Pad11)") (class "Default")
      (node (ref "U4") (pin "11") (pinfunction "PA6_11") (pintype "passive"))
    )
    (net (code "83") (name "unconnected-(U4-PA7-Pad12)") (class "Default")
      (node (ref "U4") (pin "12") (pinfunction "PA7_12") (pintype "passive"))
    )
    (net (code "84") (name "unconnected-(U4-PA8-Pad31)") (class "Default")
      (node (ref "U4") (pin "31") (pinfunction "PA8_31") (pintype "passive"))
    )
    (net (code "85") (name "unconnected-(U4-PA15-Pad36)") (class "Default")
      (node (ref "U4") (pin "36") (pinfunction "PA15_36") (pintype "passive"))
    )
    (net (code "86") (name "unconnected-(U4-PB0-Pad13)") (class "Default")
      (node (ref "U4") (pin "13") (pinfunction "PB0_13") (pintype "passive"))
    )
    (net (code "87") (name "unconnected-(U4-PB1-Pad14)") (class "Default")
      (node (ref "U4") (pin "14") (pinfunction "PB1_14") (pintype "passive"))
    )
    (net (code "88") (name "unconnected-(U4-PB3-Pad37)") (class "Default")
      (node (ref "U4") (pin "37") (pinfunction "PB3_37") (pintype "passive"))
    )
    (net (code "89") (name "unconnected-(U4-PB4-Pad38)") (class "Default")
      (node (ref "U4") (pin "38") (pinfunction "PB4_38") (pintype "passive"))
    )
    (net (code "90") (name "unconnected-(U4-PB5-Pad39)") (class "Default")
      (node (ref "U4") (pin "39") (pinfunction "PB5_39") (pintype "passive"))
    )
    (net (code "91") (name "unconnected-(U4-PB6-Pad40)") (class "Default")
      (node (ref "U4") (pin "40") (pinfunction "PB6_40") (pintype "passive"))
    )
    (net (code "92") (name "unconnected-(U4-PB7-Pad41)") (class "Default")
      (node (ref "U4") (pin "41") (pinfunction "PB7_41") (pintype "passive"))
    )
    (net (code "93") (name "unconnected-(U4-PB10-Pad15)") (class "Default")
      (node (ref "U4") (pin "15") (pinfunction "PB10_15") (pintype "passive"))
    )
    (net (code "94") (name "unconnected-(U4-PB11-Pad16)") (class "Default")
      (node (ref "U4") (pin "16") (pinfunction "PB11_16") (pintype "passive"))
    )
    (net (code "95") (name "unconnected-(U4-PB12-Pad27)") (class "Default")
      (node (ref "U4") (pin "27") (pinfunction "PB12_27") (pintype "passive"))
    )
    (net (code "96") (name "unconnected-(U4-PB13-Pad28)") (class "Default")
      (node (ref "U4") (pin "28") (pinfunction "PB13_28") (pintype "passive"))
    )
    (net (code "97") (name "unconnected-(U4-PB14-Pad29)") (class "Default")
      (node (ref "U4") (pin "29") (pinfunction "PB14_29") (pintype "passive"))
    )
    (net (code "98") (name "unconnected-(U4-PB15-Pad30)") (class "Default")
      (node (ref "U4") (pin "30") (pinfunction "PB15_30") (pintype "passive"))
    )
    (net (code "99") (name "unconnected-(U4-PC13-Pad2)") (class "Default")
      (node (ref "U4") (pin "2") (pinfunction "PC13_2") (pintype "passive"))
    )
    (net (code "100") (name "unconnected-(U4-PC14-Pad3)") (class "Default")
      (node (ref "U4") (pin "3") (pinfunction "PC14_3") (pintype "passive"))
    )
    (net (code "101") (name "unconnected-(U4-PC15-Pad4)") (class "Default")
      (node (ref "U4") (pin "4") (pinfunction "PC15_4") (pintype "passive"))
    )
    (net (code "102") (name "unconnected-(U4-Reset-Pad17)") (class "Default")
      (node (ref "U4") (pin "17") (pinfunction "Reset_17") (pintype "passive"))
    )
    (net (code "103") (name "unconnected-(U4-VB-Pad1)") (class "Default")
      (node (ref "U4") (pin "1") (pinfunction "VB_1") (pintype "passive"))
    )
    (net (code "104") (name "unconnected-(U5-3V3-Pad18)") (class "Default")
      (node (ref "U5") (pin "18") (pinfunction "3V3_18") (pintype "passive"))
    )
    (net (code "105") (name "unconnected-(U5-3V3-Pad46)") (class "Default")
      (node (ref "U5") (pin "46") (pinfunction "3V3_46") (pintype "passive"))
    )
    (net (code "106") (name "unconnected-(U5-PA8-Pad31)") (class "Default")
      (node (ref "U5") (pin "31") (pinfunction "PA8_31") (pintype "passive"))
    )
    (net (code "107") (name "unconnected-(U5-PA9-Pad32)") (class "Default")
      (node (ref "U5") (pin "32") (pinfunction "PA9_32") (pintype "passive"))
    )
    (net (code "108") (name "unconnected-(U5-PA10-Pad33)") (class "Default")
      (node (ref "U5") (pin "33") (pinfunction "PA10_33") (pintype "passive"))
    )
    (net (code "109") (name "unconnected-(U5-PA15-Pad36)") (class "Default")
      (node (ref "U5") (pin "36") (pinfunction "PA15_36") (pintype "passive"))
    )
    (net (code "110") (name "unconnected-(U5-PB3-Pad37)") (class "Default")
      (node (ref "U5") (pin "37") (pinfunction "PB3_37") (pintype "passive"))
    )
    (net (code "111") (name "unconnected-(U5-PB4-Pad38)") (class "Default")
      (node (ref "U5") (pin "38") (pinfunction "PB4_38") (pintype "passive"))
    )
    (net (code "112") (name "unconnected-(U5-PB5-Pad39)") (class "Default")
      (node (ref "U5") (pin "39") (pinfunction "PB5_39") (pintype "passive"))
    )
    (net (code "113") (name "unconnected-(U5-PB6-Pad40)") (class "Default")
      (node (ref "U5") (pin "40") (pinfunction "PB6_40") (pintype "passive"))
    )
    (net (code "114") (name "unconnected-(U5-PB7-Pad41)") (class "Default")
      (node (ref "U5") (pin "41") (pinfunction "PB7_41") (pintype "passive"))
    )
    (net (code "115") (name "unconnected-(U5-PB8-Pad42)") (class "Default")
      (node (ref "U5") (pin "42") (pinfunction "PB8_42") (pintype "passive"))
    )
    (net (code "116") (name "unconnected-(U5-PB9-Pad43)") (class "Default")
      (node (ref "U5") (pin "43") (pinfunction "PB9_43") (pintype "passive"))
    )
    (net (code "117") (name "unconnected-(U5-PB10-Pad15)") (class "Default")
      (node (ref "U5") (pin "15") (pinfunction "PB10_15") (pintype "passive"))
    )
    (net (code "118") (name "unconnected-(U5-PB11-Pad16)") (class "Default")
      (node (ref "U5") (pin "16") (pinfunction "PB11_16") (pintype "passive"))
    )
    (net (code "119") (name "unconnected-(U5-PB12-Pad27)") (class "Default")
      (node (ref "U5") (pin "27") (pinfunction "PB12_27") (pintype "passive"))
    )
    (net (code "120") (name "unconnected-(U5-PB13-Pad28)") (class "Default")
      (node (ref "U5") (pin "28") (pinfunction "PB13_28") (pintype "passive"))
    )
    (net (code "121") (name "unconnected-(U5-PB14-Pad29)") (class "Default")
      (node (ref "U5") (pin "29") (pinfunction "PB14_29") (pintype "passive"))
    )
    (net (code "122") (name "unconnected-(U5-PB15-Pad30)") (class "Default")
      (node (ref "U5") (pin "30") (pinfunction "PB15_30") (pintype "passive"))
    )
    (net (code "123") (name "unconnected-(U5-PC13-Pad2)") (class "Default")
      (node (ref "U5") (pin "2") (pinfunction "PC13_2") (pintype "passive"))
    )
    (net (code "124") (name "unconnected-(U5-PC14-Pad3)") (class "Default")
      (node (ref "U5") (pin "3") (pinfunction "PC14_3") (pintype "passive"))
    )
    (net (code "125") (name "unconnected-(U5-PC15-Pad4)") (class "Default")
      (node (ref "U5") (pin "4") (pinfunction "PC15_4") (pintype "passive"))
    )
    (net (code "126") (name "unconnected-(U5-Reset-Pad17)") (class "Default")
      (node (ref "U5") (pin "17") (pinfunction "Reset_17") (pintype "passive"))
    )
    (net (code "127") (name "unconnected-(U5-VB-Pad1)") (class "Default")
      (node (ref "U5") (pin "1") (pinfunction "VB_1") (pintype "passive"))
    )
    (net (code "128") (name "unconnected-(U7-VREF-Pad5)") (class "Default")
      (node (ref "U7") (pin "5") (pinfunction "VREF_5") (pintype "passive"))
    )
    (net (code "129") (name "unconnected-(U8-3V3-Pad1)") (class "Default")
      (node (ref "U8") (pin "1") (pinfunction "3V3_1") (pintype "passive"))
    )
    (net (code "130") (name "unconnected-(U8-D2-Pad4)") (class "Default")
      (node (ref "U8") (pin "4") (pinfunction "D2_4") (pintype "passive"))
    )
    (net (code "131") (name "unconnected-(U8-D4-Pad5)") (class "Default")
      (node (ref "U8") (pin "5") (pinfunction "D4_5") (pintype "passive"))
    )
    (net (code "132") (name "unconnected-(U8-D5-Pad8)") (class "Default")
      (node (ref "U8") (pin "8") (pinfunction "D5_8") (pintype "passive"))
    )
    (net (code "133") (name "unconnected-(U8-D12-Pad27)") (class "Default")
      (node (ref "U8") (pin "27") (pinfunction "D12_27") (pintype "passive"))
    )
    (net (code "134") (name "unconnected-(U8-D13-Pad28)") (class "Default")
      (node (ref "U8") (pin "28") (pinfunction "D13_28") (pintype "passive"))
    )
    (net (code "135") (name "unconnected-(U8-D14-Pad26)") (class "Default")
      (node (ref "U8") (pin "26") (pinfunction "D14_26") (pintype "passive"))
    )
    (net (code "136") (name "unconnected-(U8-D15-Pad3)") (class "Default")
      (node (ref "U8") (pin "3") (pinfunction "D15_3") (pintype "passive"))
    )
    (net (code "137") (name "unconnected-(U8-D21-Pad11)") (class "Default")
      (node (ref "U8") (pin "11") (pinfunction "D21_11") (pintype "passive"))
    )
    (net (code "138") (name "unconnected-(U8-D22-Pad14)") (class "Default")
      (node (ref "U8") (pin "14") (pinfunction "D22_14") (pintype "passive"))
    )
    (net (code "139") (name "unconnected-(U8-D23-Pad15)") (class "Default")
      (node (ref "U8") (pin "15") (pinfunction "D23_15") (pintype "passive"))
    )
    (net (code "140") (name "unconnected-(U8-D25-Pad23)") (class "Default")
      (node (ref "U8") (pin "23") (pinfunction "D25_23") (pintype "passive"))
    )
    (net (code "141") (name "unconnected-(U8-D26-Pad24)") (class "Default")
      (node (ref "U8") (pin "24") (pinfunction "D26_24") (pintype "passive"))
    )
    (net (code "142") (name "unconnected-(U8-D27-Pad25)") (class "Default")
      (node (ref "U8") (pin "25") (pinfunction "D27_25") (pintype "passive"))
    )
    (net (code "143") (name "unconnected-(U8-D32-Pad21)") (class "Default")
      (node (ref "U8") (pin "21") (pinfunction "D32_21") (pintype "passive"))
    )
    (net (code "144") (name "unconnected-(U8-D33-Pad22)") (class "Default")
      (node (ref "U8") (pin "22") (pinfunction "D33_22") (pintype "passive"))
    )
    (net (code "145") (name "unconnected-(U8-D34-Pad19)") (class "Default")
      (node (ref "U8") (pin "19") (pinfunction "D34_19") (pintype "passive"))
    )
    (net (code "146") (name "unconnected-(U8-D35-Pad20)") (class "Default")
      (node (ref "U8") (pin "20") (pinfunction "D35_20") (pintype "passive"))
    )
    (net (code "147") (name "unconnected-(U8-EN-Pad16)") (class "Default")
      (node (ref "U8") (pin "16") (pinfunction "EN_16") (pintype "passive"))
    )
    (net (code "148") (name "unconnected-(U8-RX2-Pad6)") (class "Default")
      (node (ref "U8") (pin "6") (pinfunction "RX2_6") (pintype "passive"))
    )
    (net (code "149") (name "unconnected-(U8-TX2-Pad7)") (class "Default")
      (node (ref "U8") (pin "7") (pinfunction "TX2_7") (pintype "passive"))
    )
    (net (code "150") (name "unconnected-(U8-VN-Pad18)") (class "Default")
      (node (ref "U8") (pin "18") (pinfunction "VN_18") (pintype "passive"))
    )
    (net (code "151") (name "unconnected-(U8-VP-Pad17)") (class "Default")
      (node (ref "U8") (pin "17") (pinfunction "VP_17") (pintype "passive"))
    )
    (net (code "152") (name "unconnected-(U9-3V3-Pad18)") (class "Default")
      (node (ref "U9") (pin "18") (pinfunction "3V3_18") (pintype "passive"))
    )
    (net (code "153") (name "unconnected-(U9-3V3-Pad46)") (class "Default")
      (node (ref "U9") (pin "46") (pinfunction "3V3_46") (pintype "passive"))
    )
    (net (code "154") (name "unconnected-(U9-PA1-Pad6)") (class "Default")
      (node (ref "U9") (pin "6") (pinfunction "PA1_6") (pintype "passive"))
    )
    (net (code "155") (name "unconnected-(U9-PA2-Pad7)") (class "Default")
      (node (ref "U9") (pin "7") (pinfunction "PA2_7") (pintype "passive"))
    )
    (net (code "156") (name "unconnected-(U9-PA3-Pad8)") (class "Default")
      (node (ref "U9") (pin "8") (pinfunction "PA3_8") (pintype "passive"))
    )
    (net (code "157") (name "unconnected-(U9-PA4-Pad9)") (class "Default")
      (node (ref "U9") (pin "9") (pinfunction "PA4_9") (pintype "passive"))
    )
    (net (code "158") (name "unconnected-(U9-PA5-Pad10)") (class "Default")
      (node (ref "U9") (pin "10") (pinfunction "PA5_10") (pintype "passive"))
    )
    (net (code "159") (name "unconnected-(U9-PA6-Pad11)") (class "Default")
      (node (ref "U9") (pin "11") (pinfunction "PA6_11") (pintype "passive"))
    )
    (net (code "160") (name "unconnected-(U9-PA8-Pad31)") (class "Default")
      (node (ref "U9") (pin "31") (pinfunction "PA8_31") (pintype "passive"))
    )
    (net (code "161") (name "unconnected-(U9-PA9-Pad32)") (class "Default")
      (node (ref "U9") (pin "32") (pinfunction "PA9_32") (pintype "passive"))
    )
    (net (code "162") (name "unconnected-(U9-PA10-Pad33)") (class "Default")
      (node (ref "U9") (pin "33") (pinfunction "PA10_33") (pintype "passive"))
    )
    (net (code "163") (name "unconnected-(U9-PA15-Pad36)") (class "Default")
      (node (ref "U9") (pin "36") (pinfunction "PA15_36") (pintype "passive"))
    )
    (net (code "164") (name "unconnected-(U9-PB1-Pad14)") (class "Default")
      (node (ref "U9") (pin "14") (pinfunction "PB1_14") (pintype "passive"))
    )
    (net (code "165") (name "unconnected-(U9-PB4-Pad38)") (class "Default")
      (node (ref "U9") (pin "38") (pinfunction "PB4_38") (pintype "passive"))
    )
    (net (code "166") (name "unconnected-(U9-PB5-Pad39)") (class "Default")
      (node (ref "U9") (pin "39") (pinfunction "PB5_39") (pintype "passive"))
    )
    (net (code "167") (name "unconnected-(U9-PB6-Pad40)") (class "Default")
      (node (ref "U9") (pin "40") (pinfunction "PB6_40") (pintype "passive"))
    )
    (net (code "168") (name "unconnected-(U9-PB7-Pad41)") (class "Default")
      (node (ref "U9") (pin "41") (pinfunction "PB7_41") (pintype "passive"))
    )
    (net (code "169") (name "unconnected-(U9-PB8-Pad42)") (class "Default")
      (node (ref "U9") (pin "42") (pinfunction "PB8_42") (pintype "passive"))
    )
    (net (code "170") (name "unconnected-(U9-PB9-Pad43)") (class "Default")
      (node (ref "U9") (pin "43") (pinfunction "PB9_43") (pintype "passive"))
    )
    (net (code "171") (name "unconnected-(U9-PB10-Pad15)") (class "Default")
      (node (ref "U9") (pin "15") (pinfunction "PB10_15") (pintype "passive"))
    )
    (net (code "172") (name "unconnected-(U9-PB11-Pad16)") (class "Default")
      (node (ref "U9") (pin "16") (pinfunction "PB11_16") (pintype "passive"))
    )
    (net (code "173") (name "unconnected-(U9-PB12-Pad27)") (class "Default")
      (node (ref "U9") (pin "27") (pinfunction "PB12_27") (pintype "passive"))
    )
    (net (code "174") (name "unconnected-(U9-PB13-Pad28)") (class "Default")
      (node (ref "U9") (pin "28") (pinfunction "PB13_28") (pintype "passive"))
    )
    (net (code "175") (name "unconnected-(U9-PB14-Pad29)") (class "Default")
      (node (ref "U9") (pin "29") (pinfunction "PB14_29") (pintype "passive"))
    )
    (net (code "176") (name "unconnected-(U9-PB15-Pad30)") (class "Default")
      (node (ref "U9") (pin "30") (pinfunction "PB15_30") (pintype "passive"))
    )
    (net (code "177") (name "unconnected-(U9-PC13-Pad2)") (class "Default")
      (node (ref "U9") (pin "2") (pinfunction "PC13_2") (pintype "passive"))
    )
    (net (code "178") (name "unconnected-(U9-PC14-Pad3)") (class "Default")
      (node (ref "U9") (pin "3") (pinfunction "PC14_3") (pintype "passive"))
    )
    (net (code "179") (name "unconnected-(U9-PC15-Pad4)") (class "Default")
      (node (ref "U9") (pin "4") (pinfunction "PC15_4") (pintype "passive"))
    )
    (net (code "180") (name "unconnected-(U9-Reset-Pad17)") (class "Default")
      (node (ref "U9") (pin "17") (pinfunction "Reset_17") (pintype "passive"))
    )
    (net (code "181") (name "unconnected-(U9-VB-Pad1)") (class "Default")
      (node (ref "U9") (pin "1") (pinfunction "VB_1") (pintype "passive"))
    )
    (net (code "182") (name "unconnected-(U10-3V3-Pad18)") (class "Default")
      (node (ref "U10") (pin "18") (pinfunction "3V3_18") (pintype "passive"))
    )
    (net (code "183") (name "unconnected-(U10-3V3-Pad46)") (class "Default")
      (node (ref "U10") (pin "46") (pinfunction "3V3_46") (pintype "passive"))
    )
    (net (code "184") (name "unconnected-(U10-PA7-Pad12)") (class "Default")
      (node (ref "U10") (pin "12") (pinfunction "PA7_12") (pintype "passive"))
    )
    (net (code "185") (name "unconnected-(U10-PA8-Pad31)") (class "Default")
      (node (ref "U10") (pin "31") (pinfunction "PA8_31") (pintype "passive"))
    )
    (net (code "186") (name "unconnected-(U10-PA10-Pad33)") (class "Default")
      (node (ref "U10") (pin "33") (pinfunction "PA10_33") (pintype "passive"))
    )
    (net (code "187") (name "unconnected-(U10-PA15-Pad36)") (class "Default")
      (node (ref "U10") (pin "36") (pinfunction "PA15_36") (pintype "passive"))
    )
    (net (code "188") (name "unconnected-(U10-PB0-Pad13)") (class "Default")
      (node (ref "U10") (pin "13") (pinfunction "PB0_13") (pintype "passive"))
    )
    (net (code "189") (name "unconnected-(U10-PB1-Pad14)") (class "Default")
      (node (ref "U10") (pin "14") (pinfunction "PB1_14") (pintype "passive"))
    )
    (net (code "190") (name "unconnected-(U10-PB3-Pad37)") (class "Default")
      (node (ref "U10") (pin "37") (pinfunction "PB3_37") (pintype "passive"))
    )
    (net (code "191") (name "unconnected-(U10-PB4-Pad38)") (class "Default")
      (node (ref "U10") (pin "38") (pinfunction "PB4_38") (pintype "passive"))
    )
    (net (code "192") (name "unconnected-(U10-PB5-Pad39)") (class "Default")
      (node (ref "U10") (pin "39") (pinfunction "PB5_39") (pintype "passive"))
    )
    (net (code "193") (name "unconnected-(U10-PB6-Pad40)") (class "Default")
      (node (ref "U10") (pin "40") (pinfunction "PB6_40") (pintype "passive"))
    )
    (net (code "194") (name "unconnected-(U10-PB7-Pad41)") (class "Default")
      (node (ref "U10") (pin "41") (pinfunction "PB7_41") (pintype "passive"))
    )
    (net (code "195") (name "unconnected-(U10-PB8-Pad42)") (class "Default")
      (node (ref "U10") (pin "42") (pinfunction "PB8_42") (pintype "passive"))
    )
    (net (code "196") (name "unconnected-(U10-PB9-Pad43)") (class "Default")
      (node (ref "U10") (pin "43") (pinfunction "PB9_43") (pintype "passive"))
    )
    (net (code "197") (name "unconnected-(U10-PB10-Pad15)") (class "Default")
      (node (ref "U10") (pin "15") (pinfunction "PB10_15") (pintype "passive"))
    )
    (net (code "198") (name "unconnected-(U10-PB11-Pad16)") (class "Default")
      (node (ref "U10") (pin "16") (pinfunction "PB11_16") (pintype "passive"))
    )
    (net (code "199") (name "unconnected-(U10-PB12-Pad27)") (class "Default")
      (node (ref "U10") (pin "27") (pinfunction "PB12_27") (pintype "passive"))
    )
    (net (code "200") (name "unconnected-(U10-PB13-Pad28)") (class "Default")
      (node (ref "U10") (pin "28") (pinfunction "PB13_28") (pintype "passive"))
    )
    (net (code "201") (name "unconnected-(U10-PB14-Pad29)") (class "Default")
      (node (ref "U10") (pin "29") (pinfunction "PB14_29") (pintype "passive"))
    )
    (net (code "202") (name "unconnected-(U10-PB15-Pad30)") (class "Default")
      (node (ref "U10") (pin "30") (pinfunction "PB15_30") (pintype "passive"))
    )
    (net (code "203") (name "unconnected-(U10-PC13-Pad2)") (class "Default")
      (node (ref "U10") (pin "2") (pinfunction "PC13_2") (pintype "passive"))
    )
    (net (code "204") (name "unconnected-(U10-Reset-Pad17)") (class "Default")
      (node (ref "U10") (pin "17") (pinfunction "Reset_17") (pintype "passive"))
    )
    (net (code "205") (name "unconnected-(U10-VB-Pad1)") (class "Default")
      (node (ref "U10") (pin "1") (pinfunction "VB_1") (pintype "passive"))
    )
    (net (code "206") (name "unconnected-(U11-VREF-Pad5)") (class "Default")
      (node (ref "U11") (pin "5") (pinfunction "VREF_5") (pintype "passive"))
    )
    (net (code "207") (name "unconnected-(U12-VREF-Pad5)") (class "Default")
      (node (ref "U12") (pin "5") (pinfunction "VREF_5") (pintype "passive"))
    )
    (net (code "208") (name "unconnected-(U13-IN3-Pad6)") (class "Default")
      (node (ref "U13") (pin "6") (pinfunction "IN3_6") (pintype "passive"))
    )
    (net (code "209") (name "unconnected-(U13-IN4-Pad5)") (class "Default")
      (node (ref "U13") (pin "5") (pinfunction "IN4_5") (pintype "passive"))
    )
    (net (code "210") (name "unconnected-(U13-OUT_3-Pad2)") (class "Default")
      (node (ref "U13") (pin "2") (pinfunction "OUT_3_2") (pintype "passive"))
    )
    (net (code "211") (name "unconnected-(U13-OUT_4-Pad1)") (class "Default")
      (node (ref "U13") (pin "1") (pinfunction "OUT_4_1") (pintype "passive"))
    )
  )
)
